# ESPRemote.net
KiCad netlist of a schematic drawn in EAGLE
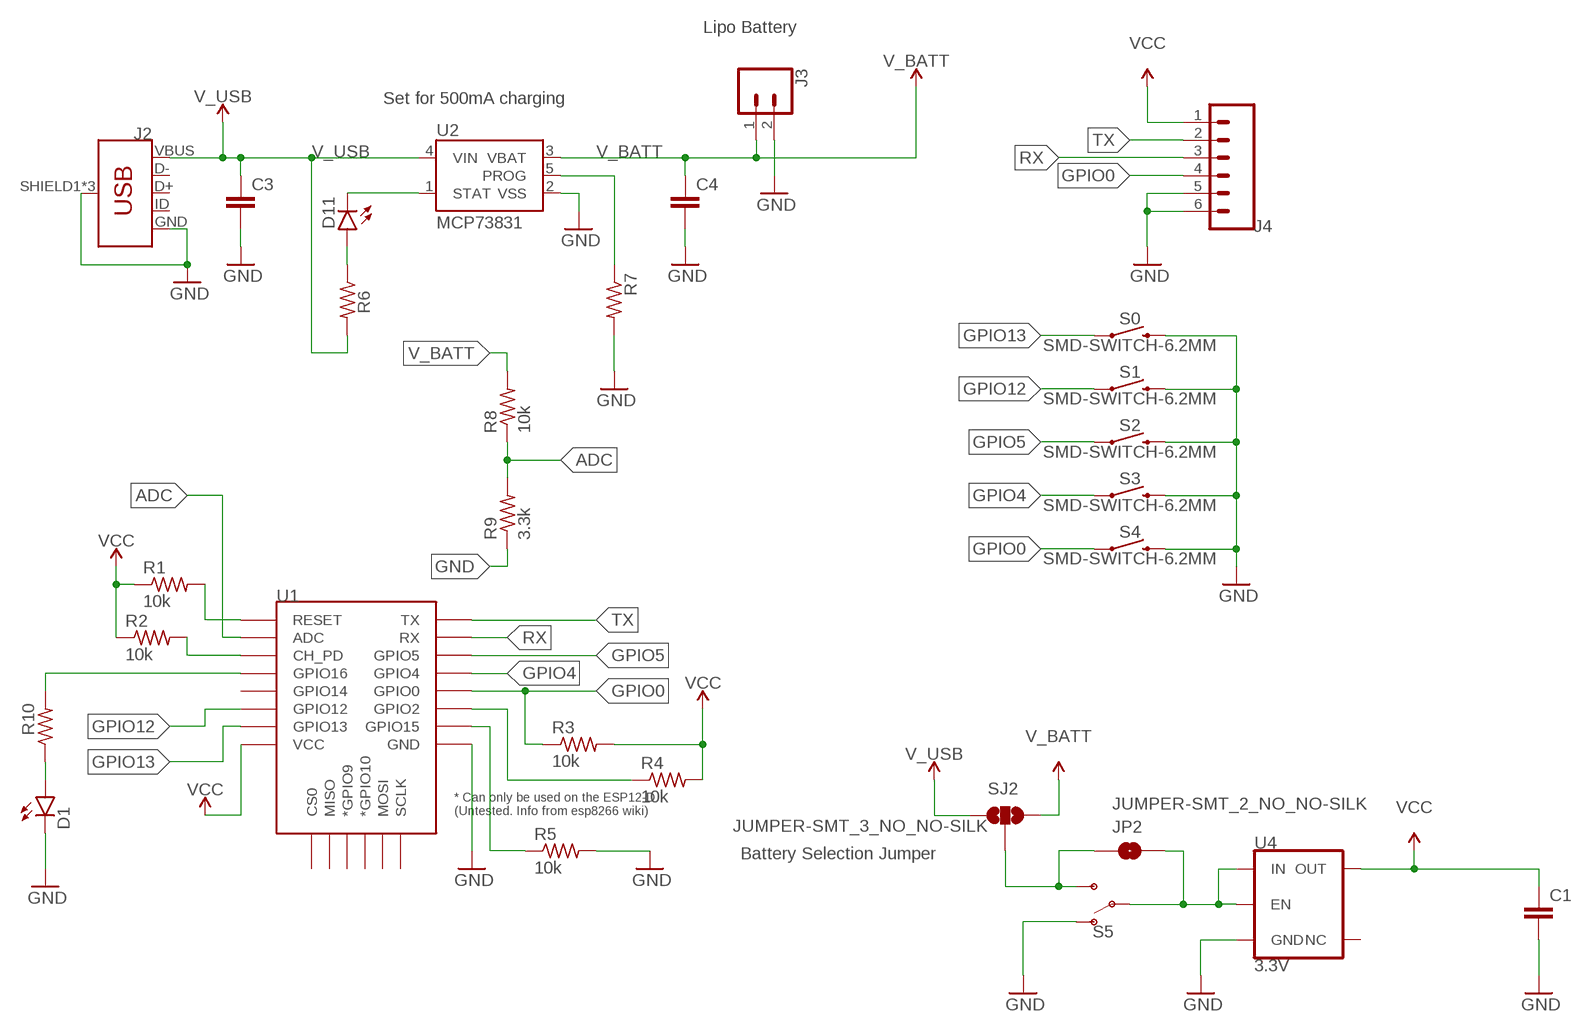
[diagram p0: schematic, sheet 1]

(export (version "E")
  (design (tool "Eeschema 10.0.6"))
  (components
    (comp (ref "C1")
      (value "10UF")
      (footprint "eagle-import:C0603")
      (libsource (lib "eagle-import") (part "10UF"))
    )
    (comp (ref "C3")
      (value "10UF")
      (footprint "eagle-import:C0603")
      (libsource (lib "eagle-import") (part "10UF"))
    )
    (comp (ref "C4")
      (value "10UF")
      (footprint "eagle-import:C0603")
      (libsource (lib "eagle-import") (part "10UF"))
    )
    (comp (ref "D1")
      (value "BLUE")
      (footprint "eagle-import:CHIP-LED0805")
      (libsource (lib "eagle-import") (part "LEDCHIP-LED0805"))
    )
    (comp (ref "D11")
      (value "RED")
      (footprint "eagle-import:CHIP-LED0805")
      (libsource (lib "eagle-import") (part "LEDCHIP-LED0805"))
    )
    (comp (ref "J2")
      (value "USB_MICRO-B_FEMALE-SMT")
      (footprint "eagle-import:USB-B-MICRO-SMD")
      (libsource (lib "eagle-import") (part "USB_MICRO-B_FEMALE-SMT"))
    )
    (comp (ref "J3")
      (value "CONN_02")
      (footprint "eagle-import:1X02")
      (libsource (lib "eagle-import") (part "CONN_02"))
    )
    (comp (ref "J4")
      (value "CONN_06SMD-1MM")
      (footprint "eagle-import:1X06-1MM")
      (libsource (lib "eagle-import") (part "CONN_06SMD-1MM"))
    )
    (comp (ref "JP2")
      (value "JUMPER-SMT_2_NO_NO-SILK")
      (footprint "eagle-import:SMT-JUMPER_2_NO_NO-SILK")
      (libsource (lib "eagle-import") (part "JUMPER-SMT_2_NO_NO-SILK"))
    )
    (comp (ref "R1")
      (value "10k")
      (footprint "eagle-import:R1206")
      (libsource (lib "eagle-import") (part "R-US_R1206"))
    )
    (comp (ref "R2")
      (value "10k")
      (footprint "eagle-import:R1206")
      (libsource (lib "eagle-import") (part "R-US_R1206"))
    )
    (comp (ref "R3")
      (value "10k")
      (footprint "eagle-import:R1206")
      (libsource (lib "eagle-import") (part "R-US_R1206"))
    )
    (comp (ref "R4")
      (value "10k")
      (footprint "eagle-import:R1206")
      (libsource (lib "eagle-import") (part "R-US_R1206"))
    )
    (comp (ref "R5")
      (value "10k")
      (footprint "eagle-import:R1206")
      (libsource (lib "eagle-import") (part "R-US_R1206"))
    )
    (comp (ref "R6")
      (value "1k")
      (footprint "eagle-import:R1206")
      (libsource (lib "eagle-import") (part "R-US_R1206"))
    )
    (comp (ref "R7")
      (value "2.0k")
      (footprint "eagle-import:R1206")
      (libsource (lib "eagle-import") (part "R-US_R1206"))
    )
    (comp (ref "R8")
      (value "10k")
      (footprint "eagle-import:R1206")
      (libsource (lib "eagle-import") (part "R-US_R1206"))
    )
    (comp (ref "R9")
      (value "3.3k")
      (footprint "eagle-import:R1206")
      (libsource (lib "eagle-import") (part "R-US_R1206"))
    )
    (comp (ref "R10")
      (value "330")
      (footprint "eagle-import:R1206")
      (libsource (lib "eagle-import") (part "R-US_R1206"))
    )
    (comp (ref "S0")
      (value "SMD-SWITCH-6.2MM")
      (footprint "eagle-import:TACTILE_SWITCH_SMD_6.0X3.5MM")
      (libsource (lib "eagle-import") (part "MOMENTARY-SWITCH-SPST-SMD-6.0X3.5MM"))
    )
    (comp (ref "S1")
      (value "SMD-SWITCH-6.2MM")
      (footprint "eagle-import:TACTILE_SWITCH_SMD_6.0X3.5MM")
      (libsource (lib "eagle-import") (part "MOMENTARY-SWITCH-SPST-SMD-6.0X3.5MM"))
    )
    (comp (ref "S2")
      (value "SMD-SWITCH-6.2MM")
      (footprint "eagle-import:TACTILE_SWITCH_SMD_6.0X3.5MM")
      (libsource (lib "eagle-import") (part "MOMENTARY-SWITCH-SPST-SMD-6.0X3.5MM"))
    )
    (comp (ref "S3")
      (value "SMD-SWITCH-6.2MM")
      (footprint "eagle-import:TACTILE_SWITCH_SMD_6.0X3.5MM")
      (libsource (lib "eagle-import") (part "MOMENTARY-SWITCH-SPST-SMD-6.0X3.5MM"))
    )
    (comp (ref "S4")
      (value "SMD-SWITCH-6.2MM")
      (footprint "eagle-import:TACTILE_SWITCH_SMD_6.0X3.5MM")
      (libsource (lib "eagle-import") (part "MOMENTARY-SWITCH-SPST-SMD-6.0X3.5MM"))
    )
    (comp (ref "S5")
      (value "SWITCH-SPDT-SMD-RIGHT-ANGLE")
      (footprint "eagle-import:SWITCH_SPST_SMD_A")
      (libsource (lib "eagle-import") (part "SWITCH-SPDT-SMD-RIGHT-ANGLE"))
    )
    (comp (ref "SJ2")
      (value "JUMPER-SMT_3_NO_NO-SILK")
      (footprint "eagle-import:SMT-JUMPER_3_NO_NO-SILK")
      (libsource (lib "eagle-import") (part "JUMPER-SMT_3_NO_NO-SILK"))
    )
    (comp (ref "U1")
      (value "ESP12ESMD")
      (footprint "eagle-import:ESP12E-SMD")
      (fields (field (name "SPICEPREFIX") "X"))
      (libsource (lib "eagle-import") (part "ESP12ESMD"))
    )
    (comp (ref "U2")
      (value "MCP73831")
      (footprint "eagle-import:SOT23-5")
      (libsource (lib "eagle-import") (part "MCP73831"))
    )
    (comp (ref "U4")
      (value "3.3V")
      (footprint "eagle-import:SOT23-5")
      (libsource (lib "eagle-import") (part "V_REG_AP2112K-3.3V"))
    )
  )
  (nets
    (net (code "1") (name "ADC") (class "Default")
      (node (ref "R8") (pin "1") (pinfunction "1_1") (pintype "passive"))
      (node (ref "R9") (pin "2") (pinfunction "2_2") (pintype "passive"))
      (node (ref "U1") (pin "ADC") (pinfunction "ADC_ADC") (pintype "bidirectional"))
    )
    (net (code "2") (name "GND") (class "Default")
      (node (ref "C1") (pin "2") (pinfunction "2_2") (pintype "passive"))
      (node (ref "C3") (pin "2") (pinfunction "2_2") (pintype "passive"))
      (node (ref "C4") (pin "2") (pinfunction "2_2") (pintype "passive"))
      (node (ref "D1") (pin "C") (pinfunction "C_C") (pintype "passive"))
      (node (ref "J2") (pin "GND") (pinfunction "GND_GND") (pintype "power_in"))
      (node (ref "J2") (pin "SHIELD1") (pinfunction "SHIELD_SHIELD1") (pintype "bidirectional"))
      (node (ref "J2") (pin "SHIELD2") (pinfunction "SHIELD_SHIELD2") (pintype "bidirectional"))
      (node (ref "J2") (pin "SHIELD3") (pinfunction "SHIELD_SHIELD3") (pintype "bidirectional"))
      (node (ref "J3") (pin "2") (pinfunction "2_2") (pintype "passive"))
      (node (ref "J4") (pin "5") (pinfunction "5_5") (pintype "passive"))
      (node (ref "J4") (pin "6") (pinfunction "6_6") (pintype "passive"))
      (node (ref "R5") (pin "2") (pinfunction "2_2") (pintype "passive"))
      (node (ref "R7") (pin "2") (pinfunction "2_2") (pintype "passive"))
      (node (ref "R9") (pin "1") (pinfunction "1_1") (pintype "passive"))
      (node (ref "S0") (pin "2") (pinfunction "2_2") (pintype "passive"))
      (node (ref "S1") (pin "2") (pinfunction "2_2") (pintype "passive"))
      (node (ref "S2") (pin "2") (pinfunction "2_2") (pintype "passive"))
      (node (ref "S3") (pin "2") (pinfunction "2_2") (pintype "passive"))
      (node (ref "S4") (pin "2") (pinfunction "2_2") (pintype "passive"))
      (node (ref "S5") (pin "1") (pinfunction "O_1") (pintype "passive"))
      (node (ref "U1") (pin "GND") (pinfunction "GND_GND") (pintype "bidirectional"))
      (node (ref "U2") (pin "2") (pinfunction "VSS_2") (pintype "power_in"))
      (node (ref "U4") (pin "2") (pinfunction "GND_2") (pintype "input"))
    )
    (net (code "3") (name "GPIO0") (class "Default")
      (node (ref "J4") (pin "4") (pinfunction "4_4") (pintype "passive"))
      (node (ref "R3") (pin "1") (pinfunction "1_1") (pintype "passive"))
      (node (ref "S4") (pin "1") (pinfunction "1_1") (pintype "passive"))
      (node (ref "U1") (pin "GPIO0") (pinfunction "GPIO0_GPIO0") (pintype "bidirectional"))
    )
    (net (code "4") (name "GPIO4") (class "Default")
      (node (ref "S3") (pin "1") (pinfunction "1_1") (pintype "passive"))
      (node (ref "U1") (pin "GPIO4") (pinfunction "GPIO4_GPIO4") (pintype "bidirectional"))
    )
    (net (code "5") (name "GPIO5") (class "Default")
      (node (ref "S2") (pin "1") (pinfunction "1_1") (pintype "passive"))
      (node (ref "U1") (pin "GPIO5") (pinfunction "GPIO5_GPIO5") (pintype "bidirectional"))
    )
    (net (code "6") (name "GPIO12") (class "Default")
      (node (ref "S1") (pin "1") (pinfunction "1_1") (pintype "passive"))
      (node (ref "U1") (pin "GPIO12") (pinfunction "GPIO12_GPIO12") (pintype "bidirectional"))
    )
    (net (code "7") (name "GPIO13") (class "Default")
      (node (ref "S0") (pin "1") (pinfunction "1_1") (pintype "passive"))
      (node (ref "U1") (pin "GPIO13") (pinfunction "GPIO13_GPIO13") (pintype "bidirectional"))
    )
    (net (code "8") (name "Net-(D1-PadA)") (class "Default")
      (node (ref "D1") (pin "A") (pinfunction "A_A") (pintype "passive"))
      (node (ref "R10") (pin "1") (pinfunction "1_1") (pintype "passive"))
    )
    (net (code "9") (name "Net-(D11-PadA)") (class "Default")
      (node (ref "D11") (pin "A") (pinfunction "A_A") (pintype "passive"))
      (node (ref "R6") (pin "1") (pinfunction "1_1") (pintype "passive"))
    )
    (net (code "10") (name "Net-(R1-Pad2)") (class "Default")
      (node (ref "R1") (pin "2") (pinfunction "2_2") (pintype "passive"))
      (node (ref "U1") (pin "RESET") (pinfunction "RESET_RESET") (pintype "bidirectional"))
    )
    (net (code "11") (name "Net-(R2-Pad2)") (class "Default")
      (node (ref "R2") (pin "2") (pinfunction "2_2") (pintype "passive"))
      (node (ref "U1") (pin "CH_PD") (pinfunction "CH_PD_CH_PD") (pintype "bidirectional"))
    )
    (net (code "12") (name "Net-(R4-Pad1)") (class "Default")
      (node (ref "R4") (pin "1") (pinfunction "1_1") (pintype "passive"))
      (node (ref "U1") (pin "GPIO2") (pinfunction "GPIO2_GPIO2") (pintype "bidirectional"))
    )
    (net (code "13") (name "Net-(R5-Pad1)") (class "Default")
      (node (ref "R5") (pin "1") (pinfunction "1_1") (pintype "passive"))
      (node (ref "U1") (pin "GPIO15") (pinfunction "GPIO15_GPIO15") (pintype "bidirectional"))
    )
    (net (code "14") (name "Net-(R10-Pad2)") (class "Default")
      (node (ref "R10") (pin "2") (pinfunction "2_2") (pintype "passive"))
      (node (ref "U1") (pin "GPIO16") (pinfunction "GPIO16_GPIO16") (pintype "bidirectional"))
    )
    (net (code "15") (name "Net-(S5-P)") (class "Default")
      (node (ref "JP2") (pin "2") (pinfunction "2_2") (pintype "passive"))
      (node (ref "S5") (pin "2") (pinfunction "P_2") (pintype "passive"))
      (node (ref "U4") (pin "1") (pinfunction "IN_1") (pintype "input"))
      (node (ref "U4") (pin "3") (pinfunction "EN_3") (pintype "input"))
    )
    (net (code "16") (name "Net-(S5-S)") (class "Default")
      (node (ref "JP2") (pin "1") (pinfunction "1_1") (pintype "passive"))
      (node (ref "S5") (pin "3") (pinfunction "S_3") (pintype "passive"))
      (node (ref "SJ2") (pin "2") (pinfunction "2_2") (pintype "passive"))
    )
    (net (code "17") (name "Net-(U2-PROG)") (class "Default")
      (node (ref "R7") (pin "1") (pinfunction "1_1") (pintype "passive"))
      (node (ref "U2") (pin "5") (pinfunction "PROG_5") (pintype "input"))
    )
    (net (code "18") (name "Net-(U2-STAT)") (class "Default")
      (node (ref "D11") (pin "C") (pinfunction "C_C") (pintype "passive"))
      (node (ref "U2") (pin "1") (pinfunction "STAT_1") (pintype "output"))
    )
    (net (code "19") (name "RX") (class "Default")
      (node (ref "J4") (pin "3") (pinfunction "3_3") (pintype "passive"))
      (node (ref "U1") (pin "RXD0") (pinfunction "RX_RXD0") (pintype "bidirectional"))
    )
    (net (code "20") (name "TX") (class "Default")
      (node (ref "J4") (pin "2") (pinfunction "2_2") (pintype "passive"))
      (node (ref "U1") (pin "TXD0") (pinfunction "TX_TXD0") (pintype "bidirectional"))
    )
    (net (code "21") (name "VCC") (class "Default")
      (node (ref "C1") (pin "1") (pinfunction "1_1") (pintype "passive"))
      (node (ref "J4") (pin "1") (pinfunction "1_1") (pintype "passive"))
      (node (ref "R1") (pin "1") (pinfunction "1_1") (pintype "passive"))
      (node (ref "R2") (pin "1") (pinfunction "1_1") (pintype "passive"))
      (node (ref "R3") (pin "2") (pinfunction "2_2") (pintype "passive"))
      (node (ref "R4") (pin "2") (pinfunction "2_2") (pintype "passive"))
      (node (ref "U1") (pin "VCC") (pinfunction "VCC_VCC") (pintype "bidirectional"))
      (node (ref "U4") (pin "5") (pinfunction "OUT_5") (pintype "passive"))
    )
    (net (code "22") (name "V_BATT") (class "Default")
      (node (ref "C4") (pin "1") (pinfunction "1_1") (pintype "passive"))
      (node (ref "J3") (pin "1") (pinfunction "1_1") (pintype "passive"))
      (node (ref "R8") (pin "2") (pinfunction "2_2") (pintype "passive"))
      (node (ref "SJ2") (pin "3") (pinfunction "3_3") (pintype "passive"))
      (node (ref "U2") (pin "3") (pinfunction "VBAT_3") (pintype "power_in"))
    )
    (net (code "23") (name "V_USB") (class "Default")
      (node (ref "C3") (pin "1") (pinfunction "1_1") (pintype "passive"))
      (node (ref "J2") (pin "VBUS") (pinfunction "VBUS_VBUS") (pintype "power_in"))
      (node (ref "R6") (pin "2") (pinfunction "2_2") (pintype "passive"))
      (node (ref "SJ2") (pin "1") (pinfunction "1_1") (pintype "passive"))
      (node (ref "U2") (pin "4") (pinfunction "VIN_4") (pintype "power_in"))
    )
    (net (code "24") (name "unconnected-(J2-PadD+)") (class "Default")
      (node (ref "J2") (pin "D+") (pinfunction "D+_D+") (pintype "bidirectional"))
    )
    (net (code "25") (name "unconnected-(J2-PadD-)") (class "Default")
      (node (ref "J2") (pin "D-") (pinfunction "D-_D-") (pintype "bidirectional"))
    )
    (net (code "26") (name "unconnected-(J2-PadID)") (class "Default")
      (node (ref "J2") (pin "ID") (pinfunction "ID_ID") (pintype "bidirectional"))
    )
    (net (code "27") (name "unconnected-(U1-*GPIO9-PadGPIO9)") (class "Default")
      (node (ref "U1") (pin "GPIO9") (pinfunction "*GPIO9_GPIO9") (pintype "bidirectional"))
    )
    (net (code "28") (name "unconnected-(U1-*GPIO10-PadGPIO10)") (class "Default")
      (node (ref "U1") (pin "GPIO10") (pinfunction "*GPIO10_GPIO10") (pintype "bidirectional"))
    )
    (net (code "29") (name "unconnected-(U1-PadCS0)") (class "Default")
      (node (ref "U1") (pin "CS0") (pinfunction "CS0_CS0") (pintype "bidirectional"))
    )
    (net (code "30") (name "unconnected-(U1-PadGPIO14)") (class "Default")
      (node (ref "U1") (pin "GPIO14") (pinfunction "GPIO14_GPIO14") (pintype "bidirectional"))
    )
    (net (code "31") (name "unconnected-(U1-PadMISO)") (class "Default")
      (node (ref "U1") (pin "MISO") (pinfunction "MISO_MISO") (pintype "bidirectional"))
    )
    (net (code "32") (name "unconnected-(U1-PadMOSI)") (class "Default")
      (node (ref "U1") (pin "MOSI") (pinfunction "MOSI_MOSI") (pintype "bidirectional"))
    )
    (net (code "33") (name "unconnected-(U1-PadSCLK)") (class "Default")
      (node (ref "U1") (pin "SCLK") (pinfunction "SCLK_SCLK") (pintype "bidirectional"))
    )
    (net (code "34") (name "unconnected-(U4-NC-Pad4)") (class "Default")
      (node (ref "U4") (pin "4") (pinfunction "NC_4") (pintype "no_connect"))
    )
  )
)
